# MCU.net
KiCad netlist of a schematic drawn in Altium Designer
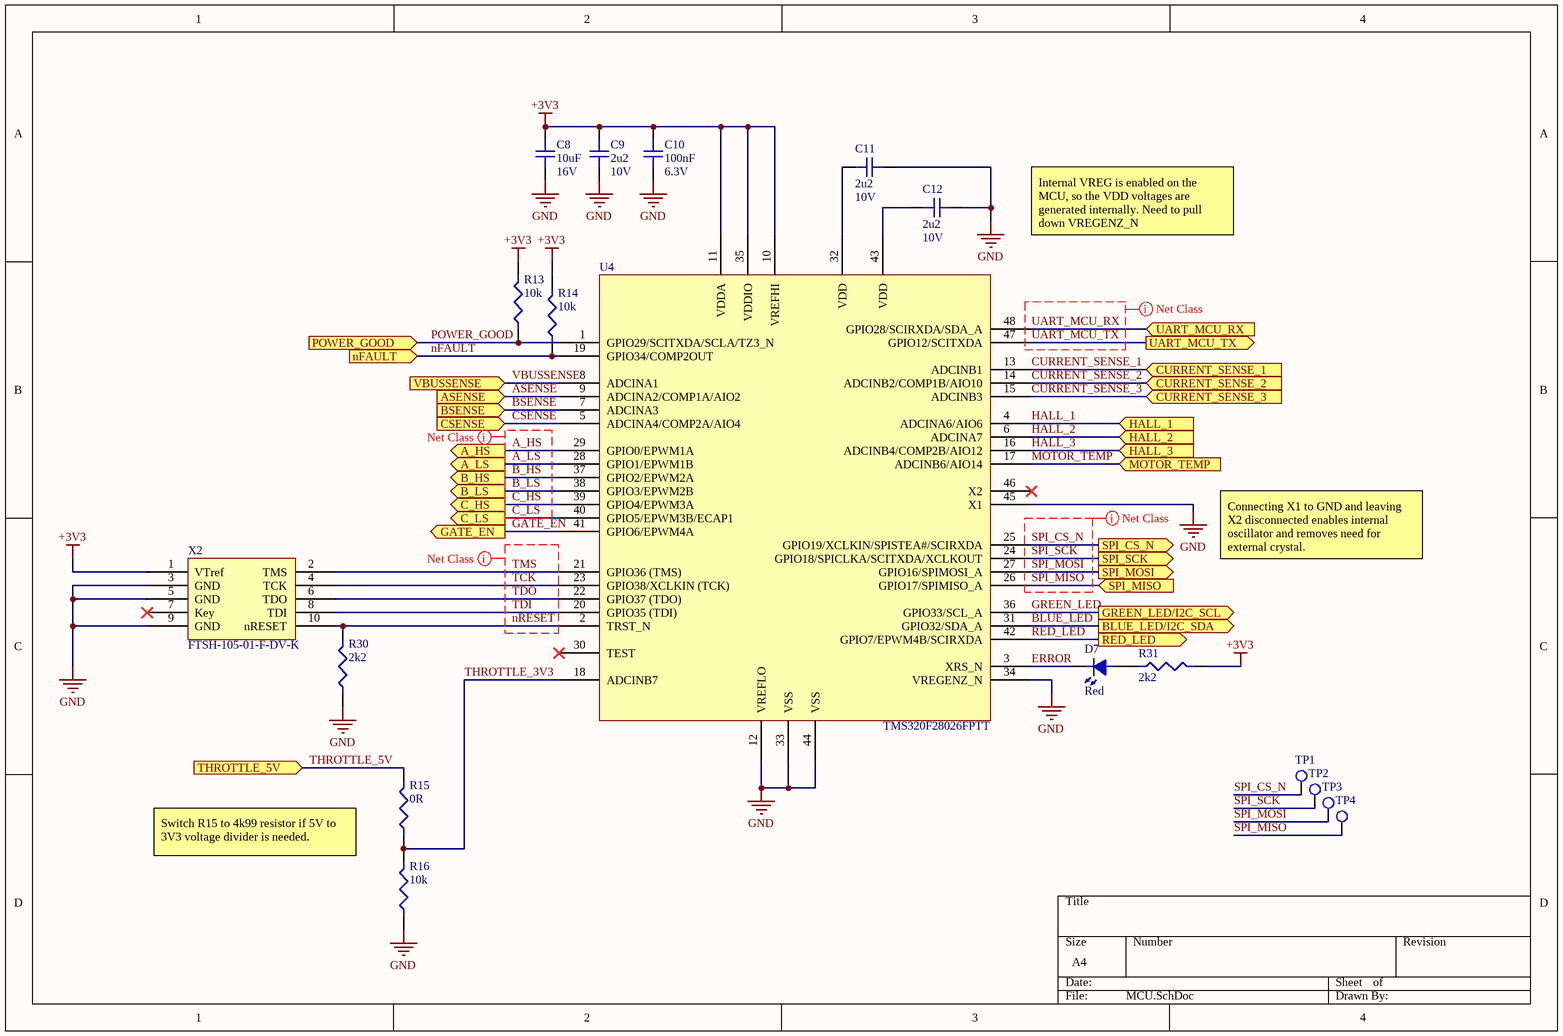
[diagram p0: MCU.SchDoc]

(export (version "E")
  (design (tool "Eeschema 10.0.6"))
  (components
    (comp (ref "C8")
      (value "10uF")
      (footprint "C0805")
      (description "CAP CER 10uF 16V X5R 10% SMD 0805 85C T/R")
      (fields
        (field (name "MANUFACTURER") "Samsung")
        (field (name "MANUFACTURER PART NUMBER") "CL21A106KOQNNNE")
        (field (name "VOLTAGE RATING") "16V")
      )
      (libsource (lib "ESC_SYMBOLS") (part "CL21A106KOQNNNE"))
    )
    (comp (ref "C9")
      (value "2u2")
      (footprint "C0402")
      (description "CAP CER 2.2uF 10V X5R 20% SMD 0402 85C Paper T/R")
      (fields
        (field (name "MANUFACTURER") "Murata")
        (field (name "MANUFACTURER PART NUMBER") "GRM155R61A225ME95D")
        (field (name "VOLTAGE RATING") "10V")
      )
      (libsource (lib "ESC_SYMBOLS") (part "GRM155R61A225ME95D"))
    )
    (comp (ref "C10")
      (value "100nF")
      (footprint "C0402")
      (description "CAP CER 0.1uF 6.3V X7R 10% SMD 0402 125C Paper T/R")
      (fields
        (field (name "MANUFACTURER") "Samsung")
        (field (name "MANUFACTURER PART NUMBER") "CL05B104KQ5NNNC")
        (field (name "VOLTAGE RATING") "6.3V")
      )
      (libsource (lib "ESC_SYMBOLS") (part "CL05B104KQ5NNNC"))
    )
    (comp (ref "C11")
      (value "2u2")
      (footprint "C0402")
      (description "CAP CER 2.2uF 10V X5R 20% SMD 0402 85C Paper T/R")
      (fields
        (field (name "MANUFACTURER") "Murata")
        (field (name "MANUFACTURER PART NUMBER") "GRM155R61A225ME95D")
        (field (name "VOLTAGE RATING") "10V")
      )
      (libsource (lib "ESC_SYMBOLS") (part "GRM155R61A225ME95D"))
    )
    (comp (ref "C12")
      (value "2u2")
      (footprint "C0402")
      (description "CAP CER 2.2uF 10V X5R 20% SMD 0402 85C Paper T/R")
      (fields
        (field (name "MANUFACTURER") "Murata")
        (field (name "MANUFACTURER PART NUMBER") "GRM155R61A225ME95D")
        (field (name "VOLTAGE RATING") "10V")
      )
      (libsource (lib "ESC_SYMBOLS") (part "GRM155R61A225ME95D"))
    )
    (comp (ref "D7")
      (value "Red")
      (footprint "LED_0603")
      (description "LED RED CLEAR 0603 SMD")
      (fields
        (field (name "MANUFACTURER") "Vishay Lite-On")
        (field (name "MANUFACTURER PART NUMBER") "LTST-C191KRKT")
      )
      (libsource (lib "ESC_SYMBOLS") (part "LTST-C191KRKT"))
    )
    (comp (ref "R13")
      (value "10k")
      (footprint "R0402")
      (description "RES SMD 10K OHM 5% 1/16W 0402")
      (fields
        (field (name "MANUFACTURER") "Yageo")
        (field (name "MANUFACTURER PART NUMBER") "RC0402JR-0710KL")
      )
      (libsource (lib "ESC_SYMBOLS") (part "RC0402JR-0710KL"))
    )
    (comp (ref "R14")
      (value "10k")
      (footprint "R0402")
      (description "RES SMD 10K OHM 5% 1/16W 0402")
      (fields
        (field (name "MANUFACTURER") "Yageo")
        (field (name "MANUFACTURER PART NUMBER") "RC0402JR-0710KL")
      )
      (libsource (lib "ESC_SYMBOLS") (part "RC0402JR-0710KL"))
    )
    (comp (ref "R15")
      (value "0R")
      (footprint "R0402")
      (description "RES SMD 0 OHM 1/16W 0402")
      (fields
        (field (name "MANUFACTURER") "Yageo")
        (field (name "MANUFACTURER PART NUMBER") "RC0402JR-070RL")
      )
      (libsource (lib "ESC_SYMBOLS") (part "RC0402JR-070RL"))
    )
    (comp (ref "R16")
      (value "10k")
      (footprint "R0402")
      (description "RES SMD 10K OHM 5% 1/16W 0402")
      (fields
        (field (name "MANUFACTURER") "Yageo")
        (field (name "MANUFACTURER PART NUMBER") "RC0402JR-0710KL")
      )
      (libsource (lib "ESC_SYMBOLS") (part "RC0402JR-0710KL"))
    )
    (comp (ref "R30")
      (value "2k2")
      (footprint "R0402")
      (description "RES SMD 2.2K OHM 5% 1/16W 0402")
      (fields
        (field (name "MANUFACTURER") "Yageo")
        (field (name "MANUFACTURER PART NUMBER") "RC0402JR-072K2L")
      )
      (libsource (lib "ESC_SYMBOLS") (part "RC0402JR-072K2L"))
    )
    (comp (ref "R31")
      (value "2k2")
      (footprint "R0402")
      (description "RES SMD 2.2K OHM 5% 1/16W 0402")
      (fields
        (field (name "MANUFACTURER") "Yageo")
        (field (name "MANUFACTURER PART NUMBER") "RC0402JR-072K2L")
      )
      (libsource (lib "ESC_SYMBOLS") (part "RC0402JR-072K2L"))
    )
    (comp (ref "TP1")
      (value "5015")
      (footprint "TP_HOOK")
      (description "TEST POINT, PCB, SMT")
      (fields (field (name "MANUFACTURER") "Keystone Electronics"))
      (libsource (lib "ESC_SYMBOLS") (part "5015"))
    )
    (comp (ref "TP2")
      (value "5015")
      (footprint "TP_HOOK")
      (description "TEST POINT, PCB, SMT")
      (fields (field (name "MANUFACTURER") "Keystone Electronics"))
      (libsource (lib "ESC_SYMBOLS") (part "5015"))
    )
    (comp (ref "TP3")
      (value "5015")
      (footprint "TP_HOOK")
      (description "TEST POINT, PCB, SMT")
      (fields (field (name "MANUFACTURER") "Keystone Electronics"))
      (libsource (lib "ESC_SYMBOLS") (part "5015"))
    )
    (comp (ref "TP4")
      (value "5015")
      (footprint "TP_HOOK")
      (description "TEST POINT, PCB, SMT")
      (fields (field (name "MANUFACTURER") "Keystone Electronics"))
      (libsource (lib "ESC_SYMBOLS") (part "5015"))
    )
    (comp (ref "U4")
      (value "TMS320F28026FPTT")
      (footprint "PQFP-48")
      (description "IC MCU 32-bit Piccolo F2802x C28x RISC 32KB Flash 3.3V 48-Pin LQFP T/R")
      (fields (field (name "MANUFACTURER") "Texas Instruments"))
      (libsource (lib "ESC_SYMBOLS") (part "TMS320F28026FPTT"))
    )
    (comp (ref "X2")
      (value "FTSH-105-01-F-DV-K")
      (footprint "JTAG_50mil_10pin")
      (description "CONN_JTAG_10pin .050 Connector Dual Header 10 Position Surface Mount")
      (fields (field (name "MANUFACTURER") "Samtec"))
      (libsource (lib "ESC_SYMBOLS") (part "FTSH-105-01-F-DV-K"))
    )
  )
  (nets
    (net (code "1") (name "+3V3") (class "Default")
      (node (ref "C10") (pin "2") (pinfunction "2_2") (pintype "passive"))
      (node (ref "C8") (pin "2") (pinfunction "2_2") (pintype "passive"))
      (node (ref "C9") (pin "2") (pinfunction "2_2") (pintype "passive"))
      (node (ref "R13") (pin "2") (pinfunction "2_2") (pintype "passive"))
      (node (ref "R14") (pin "2") (pinfunction "2_2") (pintype "passive"))
      (node (ref "R31") (pin "2") (pinfunction "2_2") (pintype "passive"))
      (node (ref "U4") (pin "10") (pinfunction "VREFHI_10") (pintype "passive"))
      (node (ref "U4") (pin "11") (pinfunction "VDDA_11") (pintype "passive"))
      (node (ref "U4") (pin "35") (pinfunction "VDDIO_35") (pintype "passive"))
      (node (ref "X2") (pin "1") (pinfunction "VTref_1") (pintype "passive"))
    )
    (net (code "2") (name "/ASENSE") (class "Default")
      (node (ref "U4") (pin "9") (pinfunction "ADCINA2/COMP1A/AIO2_9") (pintype "passive"))
    )
    (net (code "3") (name "/A_HS") (class "Default")
      (node (ref "U4") (pin "29") (pinfunction "GPIO0/EPWM1A_29") (pintype "passive"))
    )
    (net (code "4") (name "/A_LS") (class "Default")
      (node (ref "U4") (pin "28") (pinfunction "GPIO1/EPWM1B_28") (pintype "passive"))
    )
    (net (code "5") (name "/BLUE_LED") (class "Default")
      (node (ref "U4") (pin "31") (pinfunction "GPIO32/SDA_A_31") (pintype "passive"))
    )
    (net (code "6") (name "/BSENSE") (class "Default")
      (node (ref "U4") (pin "7") (pinfunction "ADCINA3_7") (pintype "passive"))
    )
    (net (code "7") (name "/B_HS") (class "Default")
      (node (ref "U4") (pin "37") (pinfunction "GPIO2/EPWM2A_37") (pintype "passive"))
    )
    (net (code "8") (name "/B_LS") (class "Default")
      (node (ref "U4") (pin "38") (pinfunction "GPIO3/EPWM2B_38") (pintype "passive"))
    )
    (net (code "9") (name "/CSENSE") (class "Default")
      (node (ref "U4") (pin "5") (pinfunction "ADCINA4/COMP2A/AIO4_5") (pintype "passive"))
    )
    (net (code "10") (name "/CURRENT_SENSE_1") (class "Default")
      (node (ref "U4") (pin "13") (pinfunction "ADCINB1_13") (pintype "passive"))
    )
    (net (code "11") (name "/CURRENT_SENSE_2") (class "Default")
      (node (ref "U4") (pin "14") (pinfunction "ADCINB2/COMP1B/AIO10_14") (pintype "passive"))
    )
    (net (code "12") (name "/CURRENT_SENSE_3") (class "Default")
      (node (ref "U4") (pin "15") (pinfunction "ADCINB3_15") (pintype "passive"))
    )
    (net (code "13") (name "/C_HS") (class "Default")
      (node (ref "U4") (pin "39") (pinfunction "GPIO4/EPWM3A_39") (pintype "passive"))
    )
    (net (code "14") (name "/C_LS") (class "Default")
      (node (ref "U4") (pin "40") (pinfunction "GPIO5/EPWM3B/ECAP1_40") (pintype "passive"))
    )
    (net (code "15") (name "/ERROR") (class "Default")
      (node (ref "D7") (pin "2") (pinfunction "2_2") (pintype "passive"))
      (node (ref "U4") (pin "3") (pinfunction "XRS_N_3") (pintype "passive"))
    )
    (net (code "16") (name "/GATE_EN") (class "Default")
      (node (ref "U4") (pin "41") (pinfunction "GPIO6/EPWM4A_41") (pintype "passive"))
    )
    (net (code "17") (name "/GREEN_LED") (class "Default")
      (node (ref "U4") (pin "36") (pinfunction "GPIO33/SCL_A_36") (pintype "passive"))
    )
    (net (code "18") (name "/HALL_1") (class "Default")
      (node (ref "U4") (pin "4") (pinfunction "ADCINA6/AIO6_4") (pintype "passive"))
    )
    (net (code "19") (name "/HALL_2") (class "Default")
      (node (ref "U4") (pin "6") (pinfunction "ADCINA7_6") (pintype "passive"))
    )
    (net (code "20") (name "/HALL_3") (class "Default")
      (node (ref "U4") (pin "16") (pinfunction "ADCINB4/COMP2B/AIO12_16") (pintype "passive"))
    )
    (net (code "21") (name "/MOTOR_TEMP") (class "Default")
      (node (ref "U4") (pin "17") (pinfunction "ADCINB6/AIO14_17") (pintype "passive"))
    )
    (net (code "22") (name "/POWER_GOOD") (class "Default")
      (node (ref "R13") (pin "1") (pinfunction "1_1") (pintype "passive"))
      (node (ref "U4") (pin "1") (pinfunction "GPIO29/SCITXDA/SCLA/TZ3_N_1") (pintype "passive"))
    )
    (net (code "23") (name "/RED_LED") (class "Default")
      (node (ref "U4") (pin "42") (pinfunction "GPIO7/EPWM4B/SCIRXDA_42") (pintype "passive"))
    )
    (net (code "24") (name "/SPI_CS_N") (class "Default")
      (node (ref "TP1") (pin "1") (pinfunction "1_1") (pintype "passive"))
      (node (ref "U4") (pin "25") (pinfunction "GPIO19/XCLKIN/SPISTEA#/SCIRXDA_25") (pintype "passive"))
    )
    (net (code "25") (name "/SPI_MISO") (class "Default")
      (node (ref "TP4") (pin "1") (pinfunction "1_1") (pintype "passive"))
      (node (ref "U4") (pin "26") (pinfunction "GPIO17/SPIMISO_A_26") (pintype "passive"))
    )
    (net (code "26") (name "/SPI_MOSI") (class "Default")
      (node (ref "TP3") (pin "1") (pinfunction "1_1") (pintype "passive"))
      (node (ref "U4") (pin "27") (pinfunction "GPIO16/SPIMOSI_A_27") (pintype "passive"))
    )
    (net (code "27") (name "/SPI_SCK") (class "Default")
      (node (ref "TP2") (pin "1") (pinfunction "1_1") (pintype "passive"))
      (node (ref "U4") (pin "24") (pinfunction "GPIO18/SPICLKA/SCITXDA/XCLKOUT_24") (pintype "passive"))
    )
    (net (code "28") (name "/TCK") (class "Default")
      (node (ref "U4") (pin "23") (pinfunction "GPIO38/XCLKIN_(TCK)_23") (pintype "passive"))
      (node (ref "X2") (pin "4") (pinfunction "TCK_4") (pintype "passive"))
    )
    (net (code "29") (name "/TDI") (class "Default")
      (node (ref "U4") (pin "20") (pinfunction "GPIO35_(TDI)_20") (pintype "passive"))
      (node (ref "X2") (pin "8") (pinfunction "TDI_8") (pintype "passive"))
    )
    (net (code "30") (name "/TDO") (class "Default")
      (node (ref "U4") (pin "22") (pinfunction "GPIO37_(TDO)_22") (pintype "passive"))
      (node (ref "X2") (pin "6") (pinfunction "TDO_6") (pintype "passive"))
    )
    (net (code "31") (name "/THROTTLE_3V3") (class "Default")
      (node (ref "R15") (pin "1") (pinfunction "1_1") (pintype "passive"))
      (node (ref "R16") (pin "2") (pinfunction "2_2") (pintype "passive"))
      (node (ref "U4") (pin "18") (pinfunction "ADCINB7_18") (pintype "passive"))
    )
    (net (code "32") (name "/THROTTLE_5V") (class "Default")
      (node (ref "R15") (pin "2") (pinfunction "2_2") (pintype "passive"))
    )
    (net (code "33") (name "/TMS") (class "Default")
      (node (ref "U4") (pin "21") (pinfunction "GPIO36_(TMS)_21") (pintype "passive"))
      (node (ref "X2") (pin "2") (pinfunction "TMS_2") (pintype "passive"))
    )
    (net (code "34") (name "/UART_MCU_RX") (class "Default")
      (node (ref "U4") (pin "48") (pinfunction "GPIO28/SCIRXDA/SDA_A_48") (pintype "passive"))
    )
    (net (code "35") (name "/UART_MCU_TX") (class "Default")
      (node (ref "U4") (pin "47") (pinfunction "GPIO12/SCITXDA_47") (pintype "passive"))
    )
    (net (code "36") (name "/VBUSSENSE") (class "Default")
      (node (ref "U4") (pin "8") (pinfunction "ADCINA1_8") (pintype "passive"))
    )
    (net (code "37") (name "/nFAULT") (class "Default")
      (node (ref "R14") (pin "1") (pinfunction "1_1") (pintype "passive"))
      (node (ref "U4") (pin "19") (pinfunction "GPIO34/COMP2OUT_19") (pintype "passive"))
    )
    (net (code "38") (name "/nRESET") (class "Default")
      (node (ref "R30") (pin "2") (pinfunction "2_2") (pintype "passive"))
      (node (ref "U4") (pin "2") (pinfunction "TRST_N_2") (pintype "passive"))
      (node (ref "X2") (pin "10") (pinfunction "nRESET_10") (pintype "passive"))
    )
    (net (code "39") (name "GND") (class "Default")
      (node (ref "C10") (pin "1") (pinfunction "1_1") (pintype "passive"))
      (node (ref "C11") (pin "2") (pinfunction "2_2") (pintype "passive"))
      (node (ref "C12") (pin "2") (pinfunction "2_2") (pintype "passive"))
      (node (ref "C8") (pin "1") (pinfunction "1_1") (pintype "passive"))
      (node (ref "C9") (pin "1") (pinfunction "1_1") (pintype "passive"))
      (node (ref "R16") (pin "1") (pinfunction "1_1") (pintype "passive"))
      (node (ref "R30") (pin "1") (pinfunction "1_1") (pintype "passive"))
      (node (ref "U4") (pin "12") (pinfunction "VREFLO_12") (pintype "passive"))
      (node (ref "U4") (pin "33") (pinfunction "VSS_33") (pintype "passive"))
      (node (ref "U4") (pin "34") (pinfunction "VREGENZ_N_34") (pintype "passive"))
      (node (ref "U4") (pin "44") (pinfunction "VSS_44") (pintype "passive"))
      (node (ref "U4") (pin "45") (pinfunction "X1_45") (pintype "passive"))
      (node (ref "X2") (pin "3") (pinfunction "GND_3") (pintype "passive"))
      (node (ref "X2") (pin "5") (pinfunction "GND_5") (pintype "passive"))
      (node (ref "X2") (pin "9") (pinfunction "GND_9") (pintype "passive"))
    )
    (net (code "40") (name "Net-(C11-Pad1)") (class "Default")
      (node (ref "C11") (pin "1") (pinfunction "1_1") (pintype "passive"))
      (node (ref "U4") (pin "32") (pinfunction "VDD_32") (pintype "passive"))
    )
    (net (code "41") (name "Net-(C12-Pad1)") (class "Default")
      (node (ref "C12") (pin "1") (pinfunction "1_1") (pintype "passive"))
      (node (ref "U4") (pin "43") (pinfunction "VDD_43") (pintype "passive"))
    )
    (net (code "42") (name "Net-(D7-Pad1)") (class "Default")
      (node (ref "D7") (pin "1") (pinfunction "1_1") (pintype "passive"))
      (node (ref "R31") (pin "1") (pinfunction "1_1") (pintype "passive"))
    )
    (net (code "43") (name "unconnected-(U4-TEST-Pad30)") (class "Default")
      (node (ref "U4") (pin "30") (pinfunction "TEST_30") (pintype "passive+no_connect"))
    )
    (net (code "44") (name "unconnected-(U4-X2-Pad46)") (class "Default")
      (node (ref "U4") (pin "46") (pinfunction "X2_46") (pintype "passive+no_connect"))
    )
    (net (code "45") (name "unconnected-(X2-Key-Pad7)") (class "Default")
      (node (ref "X2") (pin "7") (pinfunction "Key_7") (pintype "passive+no_connect"))
    )
  )
)
